# Amplification.net
KiCad netlist of a schematic drawn in Altium Designer
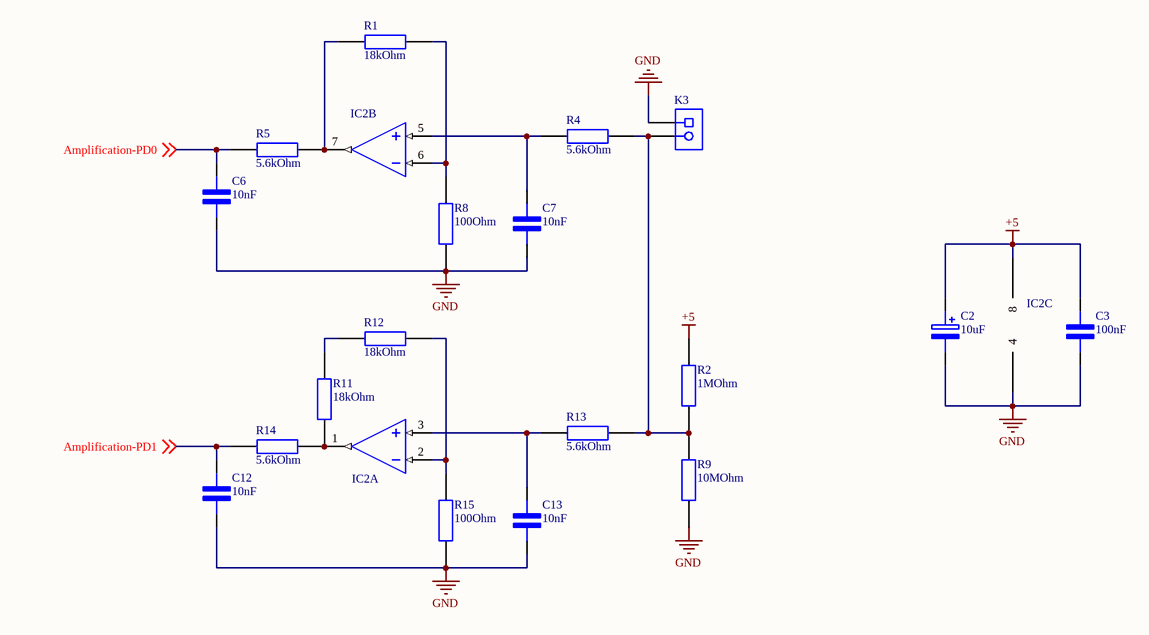
[diagram p0: Amplification.SchDoc]

(export (version "E")
  (design (tool "Eeschema 10.0.6"))
  (components
    (comp (ref "C2")
      (value "10uF")
      (footprint "10uF capacitor")
      (description "Capacitor Polarised")
      (fields
        (field (name "MOUSER2 PART NUMBER") "667-ECA-1HM100B")
        (field (name "MANUFACTURER_PART_NUMBER") "ECA-1HM100B")
      )
      (libsource (lib "Schlib1") (part "10uF capacitor"))
    )
    (comp (ref "C3")
      (value "100nF")
      (footprint "5mm lead spacing capacitor")
      (description "Capacitor")
      (fields (field (name "MANUFACTURER_PART_NUMBER") "UVR1H472MRD"))
      (libsource (lib "Schlib1") (part "100nF capacitor"))
    )
    (comp (ref "C6")
      (value "10nF")
      (footprint "5mm lead spacing capacitor")
      (description "Capacitor")
      (fields (field (name "MANUFACTURER_PART_NUMBER") "UVR1H472MRD"))
      (libsource (lib "Schlib1") (part "10nF capacitor"))
    )
    (comp (ref "C7")
      (value "10nF")
      (footprint "5mm lead spacing capacitor")
      (description "Capacitor")
      (fields (field (name "MANUFACTURER_PART_NUMBER") "UVR1H472MRD"))
      (libsource (lib "Schlib1") (part "10nF capacitor"))
    )
    (comp (ref "C12")
      (value "10nF")
      (footprint "5mm lead spacing capacitor")
      (description "Capacitor")
      (fields (field (name "MANUFACTURER_PART_NUMBER") "UVR1H472MRD"))
      (libsource (lib "Schlib1") (part "10nF capacitor"))
    )
    (comp (ref "C13")
      (value "10nF")
      (footprint "5mm lead spacing capacitor")
      (description "Capacitor")
      (fields (field (name "MANUFACTURER_PART_NUMBER") "UVR1H472MRD"))
      (libsource (lib "Schlib1") (part "10nF capacitor"))
    )
    (comp (ref "IC2")
      (value "MCP6002-E/P")
      (footprint "DIP8E")
      (description "Dual Opamp")
      (libsource (lib "Schlib1") (part "MCP6002-E/P"))
    )
    (comp (ref "K3")
      (value "1729128")
      (footprint "2-pin terminal block")
      (description "PCB Terminal Block, 13.5 A, 400 V, 2-Pin THD, RoHS, Bulk")
      (fields (field (name "MANUFACTURER") "Phoenix Contact"))
      (libsource (lib "Schlib1") (part "MKDSN 1,5/ 2-5,08"))
    )
    (comp (ref "R1")
      (value "18kOhm")
      (footprint "resistor")
      (description "Resistor")
      (fields (field (name "MANUFACTURER_PART_NUMBER") "CFR-25JT-52-10K"))
      (libsource (lib "Schlib1") (part "18kOhm resistor"))
    )
    (comp (ref "R2")
      (value "1MOhm")
      (footprint "resistor")
      (description "Resistor")
      (fields (field (name "MANUFACTURER_PART_NUMBER") "OK1055E-R52"))
      (libsource (lib "Schlib1") (part "1MOhm resistor"))
    )
    (comp (ref "R4")
      (value "5.6kOhm")
      (footprint "resistor")
      (description "Resistor")
      (fields
        (field (name "MOUSER2 PART NUMBER") "603-CFR-25JB-52-5K6")
        (field (name "MANUFACTURER_PART_NUMBER") "CFR-25JB-52-5K6")
      )
      (libsource (lib "Schlib1") (part "5.6kOhm resistor"))
    )
    (comp (ref "R5")
      (value "5.6kOhm")
      (footprint "resistor")
      (description "Resistor")
      (fields
        (field (name "MOUSER2 PART NUMBER") "603-CFR-25JB-52-5K6")
        (field (name "MANUFACTURER_PART_NUMBER") "CFR-25JB-52-5K6")
      )
      (libsource (lib "Schlib1") (part "5.6kOhm resistor"))
    )
    (comp (ref "R8")
      (value "100Ohm")
      (footprint "resistor")
      (description "Resistor")
      (fields
        (field (name "MOUSER2 PART NUMBER") "603-CFR-25JR-52100R")
        (field (name "MANUFACTURER_PART_NUMBER") "CFR-25JR-52-100R")
      )
      (libsource (lib "Schlib1") (part "100Ohm resistor"))
    )
    (comp (ref "R9")
      (value "10MOhm")
      (footprint "resistor")
      (description "Resistor")
      (fields (field (name "MANUFACTURER_PART_NUMBER") "CFR-25JT-52-10M"))
      (libsource (lib "Schlib1") (part "10MOhm resistor"))
    )
    (comp (ref "R11")
      (value "18kOhm")
      (footprint "resistor")
      (description "Resistor")
      (fields (field (name "MANUFACTURER_PART_NUMBER") "CFR-25JT-52-10K"))
      (libsource (lib "Schlib1") (part "18kOhm resistor"))
    )
    (comp (ref "R12")
      (value "18kOhm")
      (footprint "resistor")
      (description "Resistor")
      (fields (field (name "MANUFACTURER_PART_NUMBER") "CFR-25JT-52-10K"))
      (libsource (lib "Schlib1") (part "18kOhm resistor"))
    )
    (comp (ref "R13")
      (value "5.6kOhm")
      (footprint "resistor")
      (description "Resistor")
      (fields
        (field (name "MOUSER2 PART NUMBER") "603-CFR-25JB-52-5K6")
        (field (name "MANUFACTURER_PART_NUMBER") "CFR-25JB-52-5K6")
      )
      (libsource (lib "Schlib1") (part "5.6kOhm resistor"))
    )
    (comp (ref "R14")
      (value "5.6kOhm")
      (footprint "resistor")
      (description "Resistor")
      (fields
        (field (name "MOUSER2 PART NUMBER") "603-CFR-25JB-52-5K6")
        (field (name "MANUFACTURER_PART_NUMBER") "CFR-25JB-52-5K6")
      )
      (libsource (lib "Schlib1") (part "5.6kOhm resistor"))
    )
    (comp (ref "R15")
      (value "100Ohm")
      (footprint "resistor")
      (description "Resistor")
      (fields
        (field (name "MOUSER2 PART NUMBER") "603-CFR-25JR-52100R")
        (field (name "MANUFACTURER_PART_NUMBER") "CFR-25JR-52-100R")
      )
      (libsource (lib "Schlib1") (part "100Ohm resistor"))
    )
  )
  (nets
    (net (code "1") (name "+5") (class "Default")
      (node (ref "C2") (pin "1") (pinfunction "+_1") (pintype "passive"))
      (node (ref "C3") (pin "2") (pinfunction "-_2") (pintype "passive"))
      (node (ref "IC2") (pin "8") (pinfunction "8_8") (pintype "passive"))
      (node (ref "R2") (pin "2") (pinfunction "2_2") (pintype "passive"))
    )
    (net (code "2") (name "Amplification-PD0") (class "Default")
      (node (ref "C6") (pin "2") (pinfunction "-_2") (pintype "passive"))
      (node (ref "R5") (pin "1") (pinfunction "1_1") (pintype "passive"))
    )
    (net (code "3") (name "Amplification-PD1") (class "Default")
      (node (ref "C12") (pin "2") (pinfunction "-_2") (pintype "passive"))
      (node (ref "R14") (pin "1") (pinfunction "1_1") (pintype "passive"))
    )
    (net (code "4") (name "GND") (class "Default")
      (node (ref "C12") (pin "1") (pinfunction "+_1") (pintype "passive"))
      (node (ref "C13") (pin "1") (pinfunction "+_1") (pintype "passive"))
      (node (ref "C2") (pin "2") (pinfunction "-_2") (pintype "passive"))
      (node (ref "C3") (pin "1") (pinfunction "+_1") (pintype "passive"))
      (node (ref "C6") (pin "1") (pinfunction "+_1") (pintype "passive"))
      (node (ref "C7") (pin "1") (pinfunction "+_1") (pintype "passive"))
      (node (ref "IC2") (pin "4") (pinfunction "4_4") (pintype "passive"))
      (node (ref "K3") (pin "1") (pinfunction "1_1") (pintype "passive"))
      (node (ref "R15") (pin "1") (pinfunction "1_1") (pintype "passive"))
      (node (ref "R8") (pin "1") (pinfunction "1_1") (pintype "passive"))
      (node (ref "R9") (pin "1") (pinfunction "1_1") (pintype "passive"))
    )
    (net (code "5") (name "Net-(C7--)") (class "Default")
      (node (ref "C7") (pin "2") (pinfunction "-_2") (pintype "passive"))
      (node (ref "IC2") (pin "5") (pinfunction "VINB+_5") (pintype "input"))
      (node (ref "R4") (pin "2") (pinfunction "2_2") (pintype "passive"))
    )
    (net (code "6") (name "Net-(C13--)") (class "Default")
      (node (ref "C13") (pin "2") (pinfunction "-_2") (pintype "passive"))
      (node (ref "IC2") (pin "3") (pinfunction "VINA+_3") (pintype "input"))
      (node (ref "R13") (pin "1") (pinfunction "1_1") (pintype "passive"))
    )
    (net (code "7") (name "Net-(IC2A-VINA-)") (class "Default")
      (node (ref "IC2") (pin "2") (pinfunction "VINA-_2") (pintype "input"))
      (node (ref "R12") (pin "2") (pinfunction "2_2") (pintype "passive"))
      (node (ref "R15") (pin "2") (pinfunction "2_2") (pintype "passive"))
    )
    (net (code "8") (name "Net-(IC2A-VOUTA)") (class "Default")
      (node (ref "IC2") (pin "1") (pinfunction "VOUTA_1") (pintype "output"))
      (node (ref "R11") (pin "1") (pinfunction "1_1") (pintype "passive"))
      (node (ref "R14") (pin "2") (pinfunction "2_2") (pintype "passive"))
    )
    (net (code "9") (name "Net-(IC2B-VINB-)") (class "Default")
      (node (ref "IC2") (pin "6") (pinfunction "VINB-_6") (pintype "input"))
      (node (ref "R1") (pin "2") (pinfunction "2_2") (pintype "passive"))
      (node (ref "R8") (pin "2") (pinfunction "2_2") (pintype "passive"))
    )
    (net (code "10") (name "Net-(IC2B-VOUTB)") (class "Default")
      (node (ref "IC2") (pin "7") (pinfunction "VOUTB_7") (pintype "output"))
      (node (ref "R1") (pin "1") (pinfunction "1_1") (pintype "passive"))
      (node (ref "R5") (pin "2") (pinfunction "2_2") (pintype "passive"))
    )
    (net (code "11") (name "Net-(K3-Pad2)") (class "Default")
      (node (ref "K3") (pin "2") (pinfunction "2_2") (pintype "passive"))
      (node (ref "R13") (pin "2") (pinfunction "2_2") (pintype "passive"))
      (node (ref "R2") (pin "1") (pinfunction "1_1") (pintype "passive"))
      (node (ref "R4") (pin "1") (pinfunction "1_1") (pintype "passive"))
      (node (ref "R9") (pin "2") (pinfunction "2_2") (pintype "passive"))
    )
    (net (code "12") (name "Net-(R11-Pad2)") (class "Default")
      (node (ref "R11") (pin "2") (pinfunction "2_2") (pintype "passive"))
      (node (ref "R12") (pin "1") (pinfunction "1_1") (pintype "passive"))
    )
  )
)
